# V-by-One.net
KiCad netlist of a schematic drawn in Altium Designer
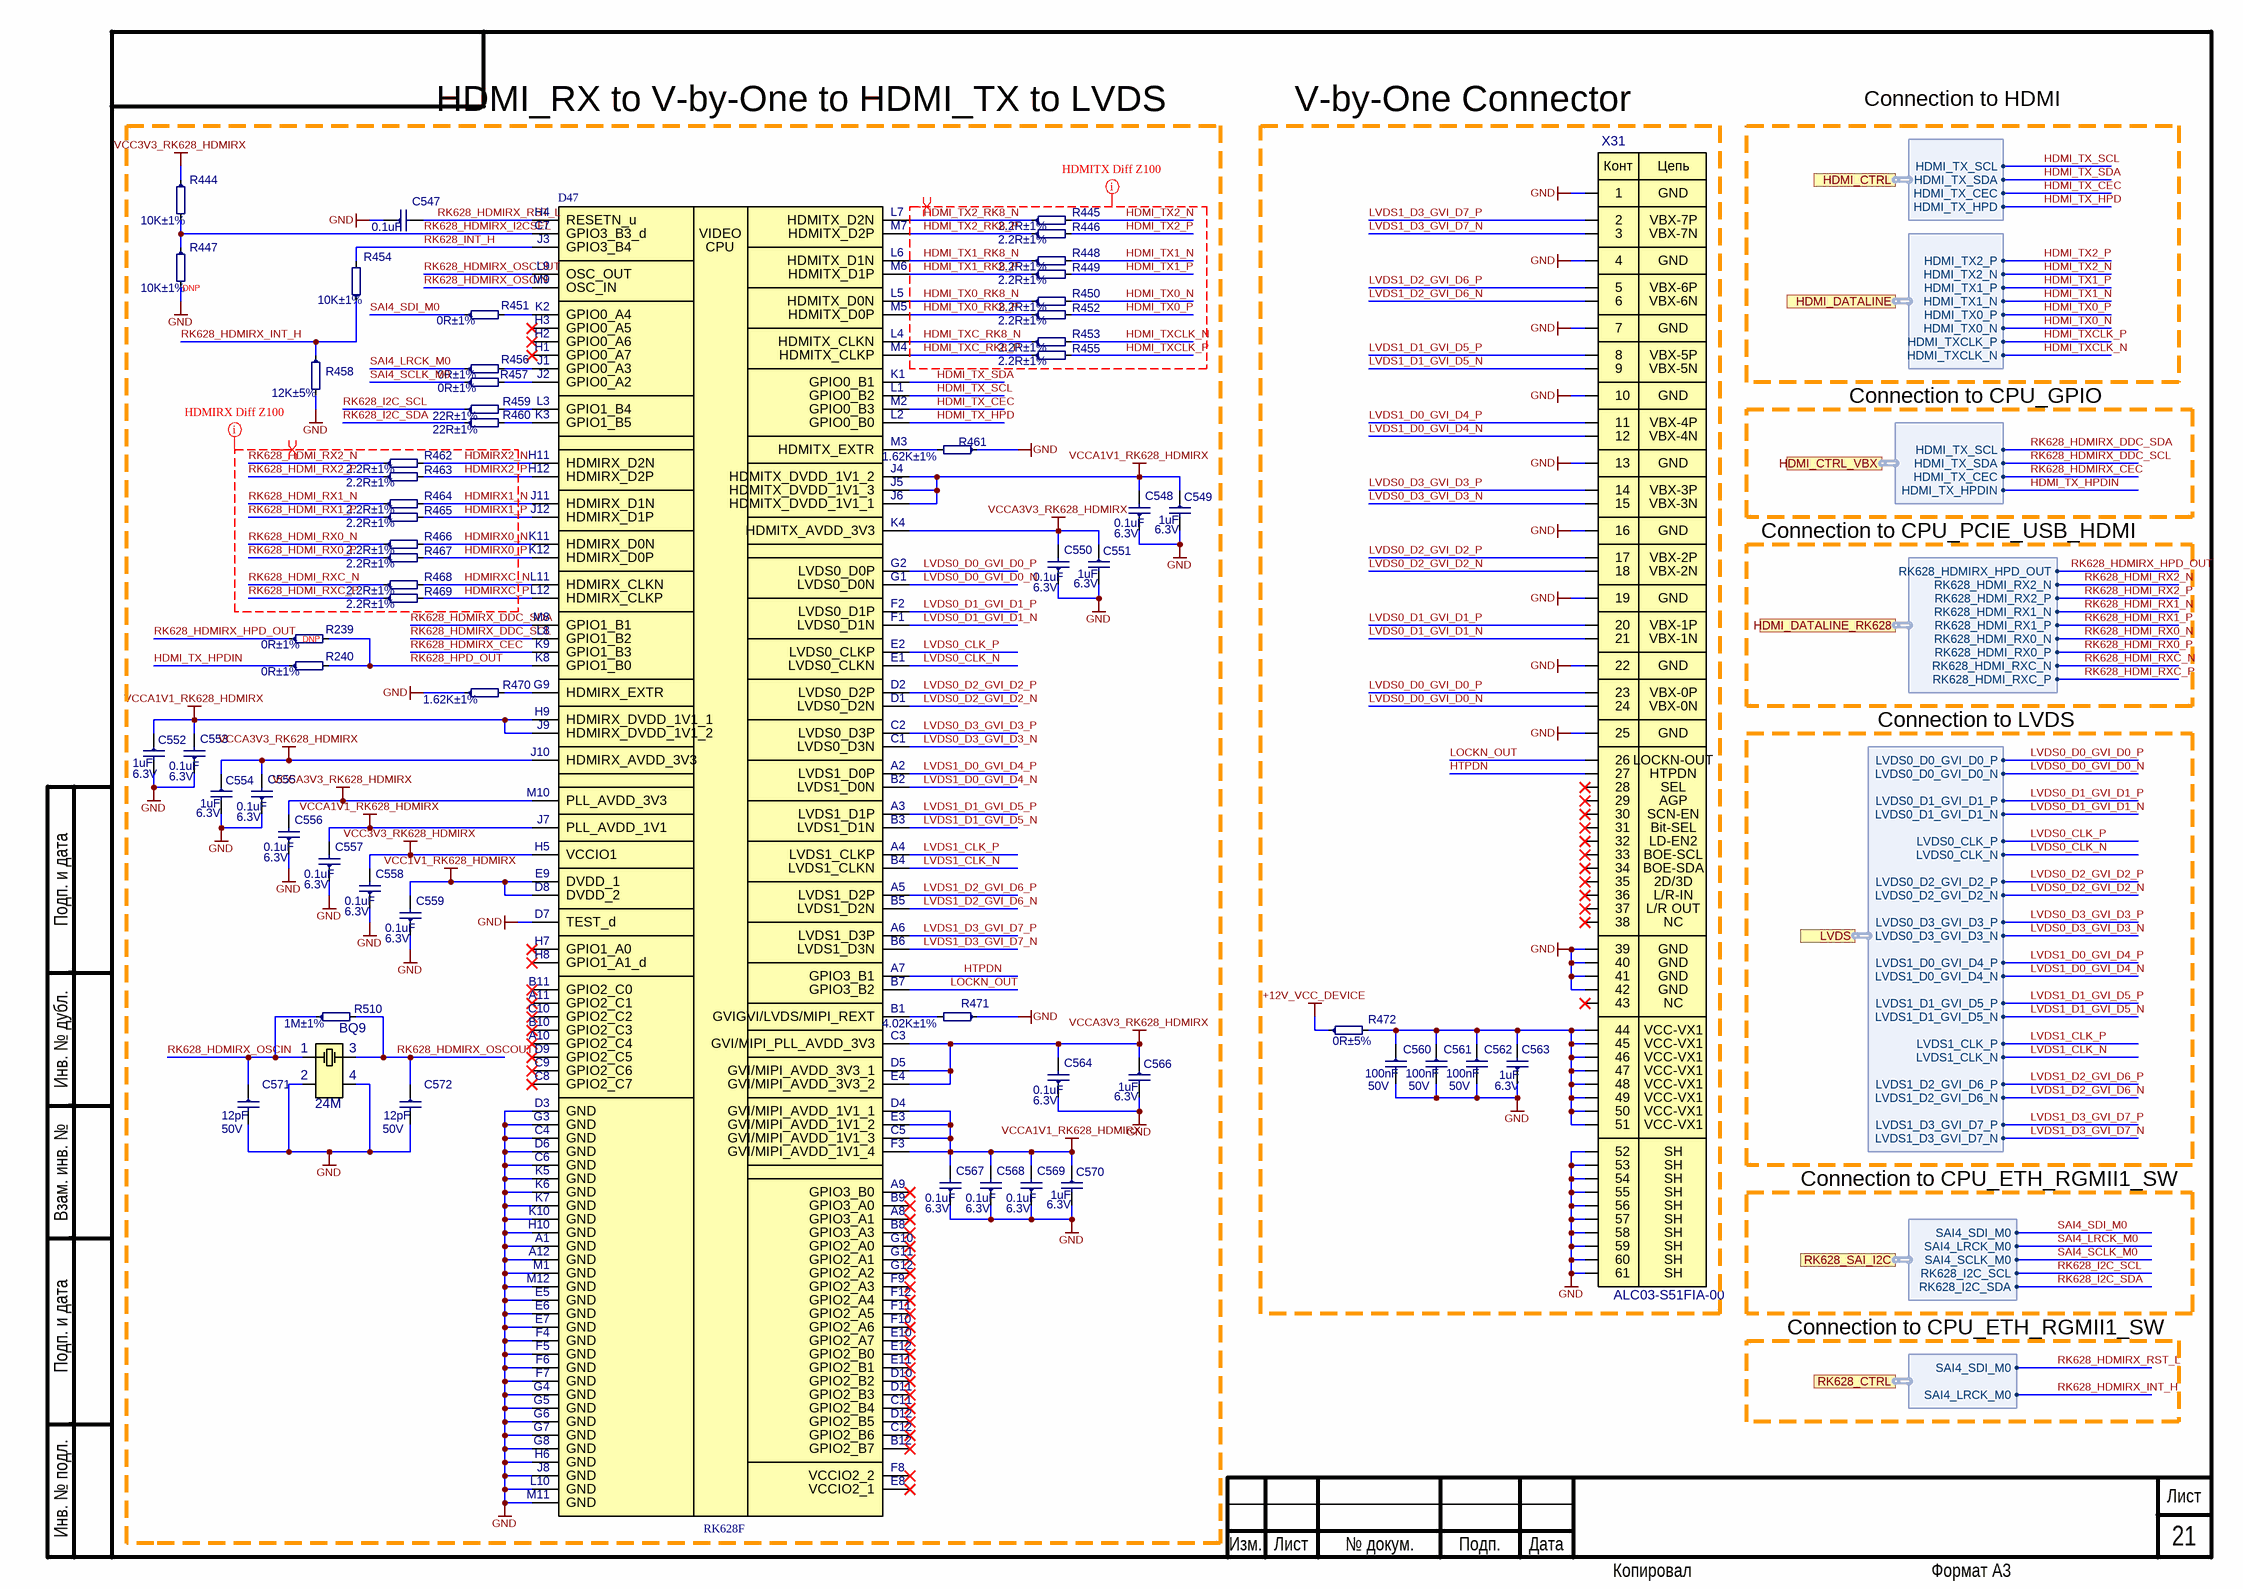
[diagram p0: V-by-One.SchDoc]

(export (version "E")
  (design (tool "Eeschema 10.0.6"))
  (components
    (comp (ref "BQ9")
      (value "24M")
      (footprint "NX3225GA")
      (fields
        (field (name "PART NUMBER") "3225-24-18-10-10/4B")
        (field (name "TOLERANCE") "10ppm")
        (field (name "MANUFACTURER") "Liming")
      )
      (libsource (lib "ATB") (part "BQ_4pin_2closed_2.4_2.4"))
    )
    (comp (ref "C547")
      (value "0.1uF")
      (footprint "C0201")
      (fields
        (field (name "VOLTAGE") "6.3V")
        (field (name "PART NUMBER") "0201-X5R-6.3V-0.1uF±10%")
        (field (name "TOLERANCE") "10%")
      )
      (libsource (lib "ATB") (part "C"))
    )
    (comp (ref "C548")
      (value "0.1uF")
      (footprint "C0201")
      (fields
        (field (name "VOLTAGE") "6.3V")
        (field (name "PART NUMBER") "0201-X5R-6.3V-0.1uF±10%")
        (field (name "TOLERANCE") "10%")
        (field (name "MANUFACTURER") "Yageo")
      )
      (libsource (lib "ATB") (part "C"))
    )
    (comp (ref "C549")
      (value "1uF")
      (footprint "C0201")
      (fields
        (field (name "VOLTAGE") "6.3V")
        (field (name "PART NUMBER") "0201-X5R-6.3V-1uF±20%")
        (field (name "TOLERANCE") "20%")
        (field (name "MANUFACTURER") "Murata Electronics")
      )
      (libsource (lib "ATB") (part "C"))
    )
    (comp (ref "C550")
      (value "0.1uF")
      (footprint "C0201")
      (fields
        (field (name "VOLTAGE") "6.3V")
        (field (name "PART NUMBER") "0201-X5R-6.3V-0.1uF±10%")
        (field (name "TOLERANCE") "10%")
        (field (name "MANUFACTURER") "Yageo")
      )
      (libsource (lib "ATB") (part "C"))
    )
    (comp (ref "C551")
      (value "1uF")
      (footprint "C0201")
      (fields
        (field (name "VOLTAGE") "6.3V")
        (field (name "PART NUMBER") "0201-X5R-6.3V-1uF±20%")
        (field (name "TOLERANCE") "20%")
        (field (name "MANUFACTURER") "Murata Electronics")
      )
      (libsource (lib "ATB") (part "C"))
    )
    (comp (ref "C552")
      (value "1uF")
      (footprint "C0201")
      (fields
        (field (name "VOLTAGE") "6.3V")
        (field (name "PART NUMBER") "0201-X5R-6.3V-1uF±20%")
        (field (name "TOLERANCE") "20%")
        (field (name "MANUFACTURER") "Murata Electronics")
      )
      (libsource (lib "ATB") (part "C"))
    )
    (comp (ref "C553")
      (value "0.1uF")
      (footprint "C0201")
      (fields
        (field (name "VOLTAGE") "6.3V")
        (field (name "PART NUMBER") "0201-X5R-6.3V-0.1uF±10%")
        (field (name "TOLERANCE") "10%")
        (field (name "MANUFACTURER") "Yageo")
      )
      (libsource (lib "ATB") (part "C"))
    )
    (comp (ref "C554")
      (value "1uF")
      (footprint "C0201")
      (fields
        (field (name "VOLTAGE") "6.3V")
        (field (name "PART NUMBER") "0201-X5R-6.3V-1uF±20%")
        (field (name "TOLERANCE") "20%")
        (field (name "MANUFACTURER") "Murata Electronics")
      )
      (libsource (lib "ATB") (part "C"))
    )
    (comp (ref "C555")
      (value "0.1uF")
      (footprint "C0201")
      (fields
        (field (name "VOLTAGE") "6.3V")
        (field (name "PART NUMBER") "0201-X5R-6.3V-0.1uF±10%")
        (field (name "TOLERANCE") "10%")
        (field (name "MANUFACTURER") "Yageo")
      )
      (libsource (lib "ATB") (part "C"))
    )
    (comp (ref "C556")
      (value "0.1uF")
      (footprint "C0201")
      (fields
        (field (name "VOLTAGE") "6.3V")
        (field (name "PART NUMBER") "0201-X5R-6.3V-0.1uF±10%")
        (field (name "TOLERANCE") "10%")
        (field (name "MANUFACTURER") "Yageo")
      )
      (libsource (lib "ATB") (part "C"))
    )
    (comp (ref "C557")
      (value "0.1uF")
      (footprint "C0201")
      (fields
        (field (name "VOLTAGE") "6.3V")
        (field (name "PART NUMBER") "0201-X5R-6.3V-0.1uF±10%")
        (field (name "TOLERANCE") "10%")
        (field (name "MANUFACTURER") "Yageo")
      )
      (libsource (lib "ATB") (part "C"))
    )
    (comp (ref "C558")
      (value "0.1uF")
      (footprint "C0201")
      (fields
        (field (name "VOLTAGE") "6.3V")
        (field (name "PART NUMBER") "0201-X5R-6.3V-0.1uF±10%")
        (field (name "TOLERANCE") "10%")
        (field (name "MANUFACTURER") "Yageo")
      )
      (libsource (lib "ATB") (part "C"))
    )
    (comp (ref "C559")
      (value "0.1uF")
      (footprint "C0201")
      (fields
        (field (name "VOLTAGE") "6.3V")
        (field (name "PART NUMBER") "0201-X5R-6.3V-0.1uF±10%")
        (field (name "TOLERANCE") "10%")
        (field (name "MANUFACTURER") "Yageo")
      )
      (libsource (lib "ATB") (part "C"))
    )
    (comp (ref "C560")
      (value "100nF")
      (footprint "C0402")
      (description "Ceramic Capacitor 0402 100nF ±10% 50V X7R")
      (fields
        (field (name "VOLTAGE") "50V")
        (field (name "PART NUMBER") "0402-X7R-50V-0.1uF±10%")
        (field (name "TOLERANCE") "10%")
      )
      (libsource (lib "ATB") (part "C"))
    )
    (comp (ref "C561")
      (value "100nF")
      (footprint "C0402")
      (description "Ceramic Capacitor 0402 100nF ±10% 50V X7R")
      (fields
        (field (name "VOLTAGE") "50V")
        (field (name "PART NUMBER") "0402-X7R-50V-0.1uF±10%")
        (field (name "TOLERANCE") "10%")
      )
      (libsource (lib "ATB") (part "C"))
    )
    (comp (ref "C562")
      (value "100nF")
      (footprint "C0402")
      (description "Ceramic Capacitor 0402 100nF ±10% 50V X7R")
      (fields
        (field (name "VOLTAGE") "50V")
        (field (name "PART NUMBER") "0402-X7R-50V-0.1uF±10%")
        (field (name "TOLERANCE") "10%")
      )
      (libsource (lib "ATB") (part "C"))
    )
    (comp (ref "C563")
      (value "1uF")
      (footprint "C0201")
      (fields
        (field (name "VOLTAGE") "6.3V")
        (field (name "PART NUMBER") "0201-X5R-6.3V-1uF±20%")
        (field (name "TOLERANCE") "20%")
        (field (name "MANUFACTURER") "Murata Electronics")
      )
      (libsource (lib "ATB") (part "C"))
    )
    (comp (ref "C564")
      (value "0.1uF")
      (footprint "C0201")
      (fields
        (field (name "VOLTAGE") "6.3V")
        (field (name "PART NUMBER") "0201-X5R-6.3V-0.1uF±10%")
        (field (name "TOLERANCE") "10%")
        (field (name "MANUFACTURER") "Yageo")
      )
      (libsource (lib "ATB") (part "C"))
    )
    (comp (ref "C566")
      (value "1uF")
      (footprint "C0201")
      (fields
        (field (name "VOLTAGE") "6.3V")
        (field (name "PART NUMBER") "0201-X5R-6.3V-1uF±20%")
        (field (name "TOLERANCE") "20%")
        (field (name "MANUFACTURER") "Murata Electronics")
      )
      (libsource (lib "ATB") (part "C"))
    )
    (comp (ref "C567")
      (value "0.1uF")
      (footprint "C0201")
      (fields
        (field (name "VOLTAGE") "6.3V")
        (field (name "PART NUMBER") "0201-X5R-6.3V-0.1uF±10%")
        (field (name "TOLERANCE") "10%")
        (field (name "MANUFACTURER") "Yageo")
      )
      (libsource (lib "ATB") (part "C"))
    )
    (comp (ref "C568")
      (value "0.1uF")
      (footprint "C0201")
      (fields
        (field (name "VOLTAGE") "6.3V")
        (field (name "PART NUMBER") "0201-X5R-6.3V-0.1uF±10%")
        (field (name "TOLERANCE") "10%")
        (field (name "MANUFACTURER") "Yageo")
      )
      (libsource (lib "ATB") (part "C"))
    )
    (comp (ref "C569")
      (value "0.1uF")
      (footprint "C0201")
      (fields
        (field (name "VOLTAGE") "6.3V")
        (field (name "PART NUMBER") "0201-X5R-6.3V-0.1uF±10%")
        (field (name "TOLERANCE") "10%")
        (field (name "MANUFACTURER") "Yageo")
      )
      (libsource (lib "ATB") (part "C"))
    )
    (comp (ref "C570")
      (value "1uF")
      (footprint "C0201")
      (fields
        (field (name "VOLTAGE") "6.3V")
        (field (name "PART NUMBER") "0201-X5R-6.3V-1uF±20%")
        (field (name "TOLERANCE") "20%")
        (field (name "MANUFACTURER") "Murata Electronics")
      )
      (libsource (lib "ATB") (part "C"))
    )
    (comp (ref "C571")
      (value "12pF")
      (footprint "C0402")
      (fields
        (field (name "VOLTAGE") "50V")
        (field (name "PART NUMBER") "0402-NP0-50V-12pF±5%")
        (field (name "TOLERANCE") "5%")
        (field (name "MANUFACTURER") "Murata Electronics")
      )
      (libsource (lib "ATB") (part "C"))
    )
    (comp (ref "C572")
      (value "12pF")
      (footprint "C0402")
      (fields
        (field (name "VOLTAGE") "50V")
        (field (name "PART NUMBER") "0402-NP0-50V-12pF±5%")
        (field (name "TOLERANCE") "5%")
        (field (name "MANUFACTURER") "Murata Electronics")
      )
      (libsource (lib "ATB") (part "C"))
    )
    (comp (ref "D47")
      (value "RK628F")
      (footprint "RK628F")
      (description "Bridge BGA-144L(8x8) Video Processing RoHS")
      (fields (field (name "MANUFACTURER") "Rockchip"))
      (libsource (lib "LIB_RK") (part "RK628F"))
    )
    (comp (ref "R239")
      (value "0R±1%")
      (footprint "R0402")
      (description "Chip Resistor 0402 0Ω ±1% 50V ±100ppm/℃ Thick Film")
      (fields (field (name "PART NUMBER") "0402-0.0625W-0R-100ppm±1%") (field (name "TOLERANCE") "1%"))
      (libsource (lib "ATB") (part "R"))
    )
    (comp (ref "R240")
      (value "0R±1%")
      (footprint "R0402")
      (description "Chip Resistor 0402 0Ω ±1% 50V ±100ppm/℃ Thick Film")
      (fields (field (name "PART NUMBER") "0402-0.0625W-0R-100ppm±1%") (field (name "TOLERANCE") "1%"))
      (libsource (lib "ATB") (part "R"))
    )
    (comp (ref "R444")
      (value "10K±1%")
      (footprint "R0402")
      (description "Chip Resistor 0402 10kΩ ±1% 50V ±100ppm/℃ Thick Film")
      (fields (field (name "PART NUMBER") "0402-0.0625W-10K-100ppm±1%") (field (name "TOLERANCE") "1%"))
      (libsource (lib "ATB") (part "R"))
    )
    (comp (ref "R445")
      (value "2.2R±1%")
      (footprint "R0402")
      (fields
        (field (name "PART NUMBER") "0402-0.0625W-2.2R-100ppm±1%")
        (field (name "TOLERANCE") "1%")
        (field (name "MANUFACTURER") "Yageo")
      )
      (libsource (lib "ATB") (part "R"))
    )
    (comp (ref "R446")
      (value "2.2R±1%")
      (footprint "R0402")
      (fields
        (field (name "PART NUMBER") "0402-0.0625W-2.2R-100ppm±1%")
        (field (name "TOLERANCE") "1%")
        (field (name "MANUFACTURER") "Yageo")
      )
      (libsource (lib "ATB") (part "R"))
    )
    (comp (ref "R447")
      (value "10K±1%")
      (footprint "R0402")
      (description "Chip Resistor 0402 10kΩ ±1% 50V ±100ppm/℃ Thick Film")
      (fields (field (name "PART NUMBER") "0402-0.0625W-10K-100ppm±1%") (field (name "TOLERANCE") "1%"))
      (libsource (lib "ATB") (part "R"))
    )
    (comp (ref "R448")
      (value "2.2R±1%")
      (footprint "R0402")
      (fields
        (field (name "PART NUMBER") "0402-0.0625W-2.2R-100ppm±1%")
        (field (name "TOLERANCE") "1%")
        (field (name "MANUFACTURER") "Yageo")
      )
      (libsource (lib "ATB") (part "R"))
    )
    (comp (ref "R449")
      (value "2.2R±1%")
      (footprint "R0402")
      (fields
        (field (name "PART NUMBER") "0402-0.0625W-2.2R-100ppm±1%")
        (field (name "TOLERANCE") "1%")
        (field (name "MANUFACTURER") "Yageo")
      )
      (libsource (lib "ATB") (part "R"))
    )
    (comp (ref "R450")
      (value "2.2R±1%")
      (footprint "R0402")
      (fields
        (field (name "PART NUMBER") "0402-0.0625W-2.2R-100ppm±1%")
        (field (name "TOLERANCE") "1%")
        (field (name "MANUFACTURER") "Yageo")
      )
      (libsource (lib "ATB") (part "R"))
    )
    (comp (ref "R451")
      (value "0R±1%")
      (footprint "R0402")
      (description "Chip Resistor 0402 0Ω ±1% 50V ±100ppm/℃ Thick Film")
      (fields (field (name "PART NUMBER") "0402-0.0625W-0R-100ppm±1%") (field (name "TOLERANCE") "1%"))
      (libsource (lib "ATB") (part "R"))
    )
    (comp (ref "R452")
      (value "2.2R±1%")
      (footprint "R0402")
      (fields
        (field (name "PART NUMBER") "0402-0.0625W-2.2R-100ppm±1%")
        (field (name "TOLERANCE") "1%")
        (field (name "MANUFACTURER") "Yageo")
      )
      (libsource (lib "ATB") (part "R"))
    )
    (comp (ref "R453")
      (value "2.2R±1%")
      (footprint "R0402")
      (fields
        (field (name "PART NUMBER") "0402-0.0625W-2.2R-100ppm±1%")
        (field (name "TOLERANCE") "1%")
        (field (name "MANUFACTURER") "Yageo")
      )
      (libsource (lib "ATB") (part "R"))
    )
    (comp (ref "R454")
      (value "10K±1%")
      (footprint "R0402")
      (description "Chip Resistor 0402 10kΩ ±1% 50V ±100ppm/℃ Thick Film")
      (fields (field (name "PART NUMBER") "0402-0.0625W-10K-100ppm±1%") (field (name "TOLERANCE") "1%"))
      (libsource (lib "ATB") (part "R"))
    )
    (comp (ref "R455")
      (value "2.2R±1%")
      (footprint "R0402")
      (fields
        (field (name "PART NUMBER") "0402-0.0625W-2.2R-100ppm±1%")
        (field (name "TOLERANCE") "1%")
        (field (name "MANUFACTURER") "Yageo")
      )
      (libsource (lib "ATB") (part "R"))
    )
    (comp (ref "R456")
      (value "0R±1%")
      (footprint "R0402")
      (description "Chip Resistor 0402 0Ω ±1% 50V ±100ppm/℃ Thick Film")
      (fields (field (name "PART NUMBER") "0402-0.0625W-0R-100ppm±1%") (field (name "TOLERANCE") "1%"))
      (libsource (lib "ATB") (part "R"))
    )
    (comp (ref "R457")
      (value "0R±1%")
      (footprint "R0402")
      (description "Chip Resistor 0402 0Ω ±1% 50V ±100ppm/℃ Thick Film")
      (fields (field (name "PART NUMBER") "0402-0.0625W-0R-100ppm±1%") (field (name "TOLERANCE") "1%"))
      (libsource (lib "ATB") (part "R"))
    )
    (comp (ref "R458")
      (value "12K±5%")
      (footprint "R0402")
      (fields
        (field (name "PART NUMBER") "0402-0.0625W-12K-100ppm±5%")
        (field (name "TOLERANCE") "5%")
        (field (name "MANUFACTURER") "Walsin Technology Corporation")
      )
      (libsource (lib "ATB") (part "R"))
    )
    (comp (ref "R459")
      (value "22R±1%")
      (footprint "R0402")
      (description "Chip Resistor 0402 22Ω ±1% 50V ±100ppm/℃ Thick Film")
      (fields (field (name "PART NUMBER") "0402-0.0625W-22R-100ppm±1%") (field (name "TOLERANCE") "1%"))
      (libsource (lib "ATB") (part "R"))
    )
    (comp (ref "R460")
      (value "22R±1%")
      (footprint "R0402")
      (description "Chip Resistor 0402 22Ω ±1% 50V ±100ppm/℃ Thick Film")
      (fields (field (name "PART NUMBER") "0402-0.0625W-22R-100ppm±1%") (field (name "TOLERANCE") "1%"))
      (libsource (lib "ATB") (part "R"))
    )
    (comp (ref "R461")
      (value "1.62K±1%")
      (footprint "R0402")
      (fields
        (field (name "PART NUMBER") "0402-0.0625W-1.62K-100ppm±1%")
        (field (name "TOLERANCE") "1%")
        (field (name "MANUFACTURER") "Yageo")
      )
      (libsource (lib "ATB") (part "R"))
    )
    (comp (ref "R462")
      (value "2.2R±1%")
      (footprint "R0402")
      (fields
        (field (name "PART NUMBER") "0402-0.0625W-2.2R-100ppm±1%")
        (field (name "TOLERANCE") "1%")
        (field (name "MANUFACTURER") "Yageo")
      )
      (libsource (lib "ATB") (part "R"))
    )
    (comp (ref "R463")
      (value "2.2R±1%")
      (footprint "R0402")
      (fields
        (field (name "PART NUMBER") "0402-0.0625W-2.2R-100ppm±1%")
        (field (name "TOLERANCE") "1%")
        (field (name "MANUFACTURER") "Yageo")
      )
      (libsource (lib "ATB") (part "R"))
    )
    (comp (ref "R464")
      (value "2.2R±1%")
      (footprint "R0402")
      (fields
        (field (name "PART NUMBER") "0402-0.0625W-2.2R-100ppm±1%")
        (field (name "TOLERANCE") "1%")
        (field (name "MANUFACTURER") "Yageo")
      )
      (libsource (lib "ATB") (part "R"))
    )
    (comp (ref "R465")
      (value "2.2R±1%")
      (footprint "R0402")
      (fields
        (field (name "PART NUMBER") "0402-0.0625W-2.2R-100ppm±1%")
        (field (name "TOLERANCE") "1%")
        (field (name "MANUFACTURER") "Yageo")
      )
      (libsource (lib "ATB") (part "R"))
    )
    (comp (ref "R466")
      (value "2.2R±1%")
      (footprint "R0402")
      (fields
        (field (name "PART NUMBER") "0402-0.0625W-2.2R-100ppm±1%")
        (field (name "TOLERANCE") "1%")
        (field (name "MANUFACTURER") "Yageo")
      )
      (libsource (lib "ATB") (part "R"))
    )
    (comp (ref "R467")
      (value "2.2R±1%")
      (footprint "R0402")
      (fields
        (field (name "PART NUMBER") "0402-0.0625W-2.2R-100ppm±1%")
        (field (name "TOLERANCE") "1%")
        (field (name "MANUFACTURER") "Yageo")
      )
      (libsource (lib "ATB") (part "R"))
    )
    (comp (ref "R468")
      (value "2.2R±1%")
      (footprint "R0402")
      (fields
        (field (name "PART NUMBER") "0402-0.0625W-2.2R-100ppm±1%")
        (field (name "TOLERANCE") "1%")
        (field (name "MANUFACTURER") "Yageo")
      )
      (libsource (lib "ATB") (part "R"))
    )
    (comp (ref "R469")
      (value "2.2R±1%")
      (footprint "R0402")
      (fields
        (field (name "PART NUMBER") "0402-0.0625W-2.2R-100ppm±1%")
        (field (name "TOLERANCE") "1%")
        (field (name "MANUFACTURER") "Yageo")
      )
      (libsource (lib "ATB") (part "R"))
    )
    (comp (ref "R470")
      (value "1.62K±1%")
      (footprint "R0402")
      (fields
        (field (name "PART NUMBER") "0402-0.0625W-1.62K-100ppm±1%")
        (field (name "TOLERANCE") "1%")
        (field (name "MANUFACTURER") "Yageo")
      )
      (libsource (lib "ATB") (part "R"))
    )
    (comp (ref "R471")
      (value "4.02K±1%")
      (footprint "R0402")
      (fields
        (field (name "PART NUMBER") "0402-0.0625W-4.02K-100ppm±1%")
        (field (name "TOLERANCE") "1%")
        (field (name "MANUFACTURER") "Yageo")
      )
      (libsource (lib "ATB") (part "R"))
    )
    (comp (ref "R472")
      (value "0R±5%")
      (footprint "R2010")
      (description "Chip Resistor 2010 0Ω ±5% 200V ±200ppm/℃ Thick Film")
      (fields (field (name "PART NUMBER") "2010-0.75W-0R-200ppm±5%") (field (name "TOLERANCE") "5%"))
      (libsource (lib "ATB") (part "R"))
    )
    (comp (ref "R510")
      (value "1M±1%")
      (footprint "R0402")
      (description "Chip Resistor 0402 1MΩ ±1% 50V ±100ppm/℃ Thick Film")
      (fields (field (name "PART NUMBER") "0402-0.0625W-1M-100ppm±1%") (field (name "TOLERANCE") "1%"))
      (libsource (lib "ATB") (part "R"))
    )
    (comp (ref "X31")
      (value "ALC03-S51FIA-00")
      (footprint "ALC03-S51FIA-00")
      (fields (field (name "MANUFACTURER") "JUSHUO"))
      (libsource (lib "LIB_RK") (part "ALC03-S51FIA-00"))
    )
  )
  (nets
    (net (code "8") (name "+12V_VCC_DEVICE") (class "Default")
      (node (ref "R472") (pin "1") (pinfunction "1_1") (pintype "passive"))
    )
    (net (code "9") (name "/HDMIRX0_N") (class "Default")
      (node (ref "D47") (pin "K11") (pinfunction "HDMIRX_D0N_K11") (pintype "passive"))
      (node (ref "R466") (pin "2") (pinfunction "2_2") (pintype "passive"))
    )
    (net (code "10") (name "/HDMIRX0_P") (class "Default")
      (node (ref "D47") (pin "K12") (pinfunction "HDMIRX_D0P_K12") (pintype "passive"))
      (node (ref "R467") (pin "2") (pinfunction "2_2") (pintype "passive"))
    )
    (net (code "11") (name "/HDMIRX1_N") (class "Default")
      (node (ref "D47") (pin "J11") (pinfunction "HDMIRX_D1N_J11") (pintype "passive"))
      (node (ref "R464") (pin "2") (pinfunction "2_2") (pintype "passive"))
    )
    (net (code "12") (name "/HDMIRX1_P") (class "Default")
      (node (ref "D47") (pin "J12") (pinfunction "HDMIRX_D1P_J12") (pintype "passive"))
      (node (ref "R465") (pin "2") (pinfunction "2_2") (pintype "passive"))
    )
    (net (code "13") (name "/HDMIRX2_N") (class "Default")
      (node (ref "D47") (pin "H11") (pinfunction "HDMIRX_D2N_H11") (pintype "passive"))
      (node (ref "R462") (pin "2") (pinfunction "2_2") (pintype "passive"))
    )
    (net (code "14") (name "/HDMIRX2_P") (class "Default")
      (node (ref "D47") (pin "H12") (pinfunction "HDMIRX_D2P_H12") (pintype "passive"))
      (node (ref "R463") (pin "2") (pinfunction "2_2") (pintype "passive"))
    )
    (net (code "15") (name "/HDMIRXC_N") (class "Default")
      (node (ref "D47") (pin "L11") (pinfunction "HDMIRX_CLKN_L11") (pintype "passive"))
      (node (ref "R468") (pin "2") (pinfunction "2_2") (pintype "passive"))
    )
    (net (code "16") (name "/HDMIRXC_P") (class "Default")
      (node (ref "D47") (pin "L12") (pinfunction "HDMIRX_CLKP_L12") (pintype "passive"))
      (node (ref "R469") (pin "2") (pinfunction "2_2") (pintype "passive"))
    )
    (net (code "17") (name "/HDMI_TX0_N") (class "Default")
      (node (ref "R450") (pin "2") (pinfunction "2_2") (pintype "passive"))
    )
    (net (code "18") (name "/HDMI_TX0_P") (class "Default")
      (node (ref "R452") (pin "2") (pinfunction "2_2") (pintype "passive"))
    )
    (net (code "19") (name "/HDMI_TX0_RK8_N") (class "Default")
      (node (ref "D47") (pin "L5") (pinfunction "HDMITX_D0N_L5") (pintype "passive"))
      (node (ref "R450") (pin "1") (pinfunction "1_1") (pintype "passive"))
    )
    (net (code "20") (name "/HDMI_TX0_RK8_P") (class "Default")
      (node (ref "D47") (pin "M5") (pinfunction "HDMITX_D0P_M5") (pintype "passive"))
      (node (ref "R452") (pin "1") (pinfunction "1_1") (pintype "passive"))
    )
    (net (code "21") (name "/HDMI_TX1_N") (class "Default")
      (node (ref "R448") (pin "2") (pinfunction "2_2") (pintype "passive"))
    )
    (net (code "22") (name "/HDMI_TX1_P") (class "Default")
      (node (ref "R449") (pin "2") (pinfunction "2_2") (pintype "passive"))
    )
    (net (code "23") (name "/HDMI_TX1_RK8_N") (class "Default")
      (node (ref "D47") (pin "L6") (pinfunction "HDMITX_D1N_L6") (pintype "passive"))
      (node (ref "R448") (pin "1") (pinfunction "1_1") (pintype "passive"))
    )
    (net (code "24") (name "/HDMI_TX1_RK8_P") (class "Default")
      (node (ref "D47") (pin "M6") (pinfunction "HDMITX_D1P_M6") (pintype "passive"))
      (node (ref "R449") (pin "1") (pinfunction "1_1") (pintype "passive"))
    )
    (net (code "25") (name "/HDMI_TX2_N") (class "Default")
      (node (ref "R445") (pin "2") (pinfunction "2_2") (pintype "passive"))
    )
    (net (code "26") (name "/HDMI_TX2_P") (class "Default")
      (node (ref "R446") (pin "2") (pinfunction "2_2") (pintype "passive"))
    )
    (net (code "27") (name "/HDMI_TX2_RK8_N") (class "Default")
      (node (ref "D47") (pin "L7") (pinfunction "HDMITX_D2N_L7") (pintype "passive"))
      (node (ref "R445") (pin "1") (pinfunction "1_1") (pintype "passive"))
    )
    (net (code "28") (name "/HDMI_TX2_RK8_P") (class "Default")
      (node (ref "D47") (pin "M7") (pinfunction "HDMITX_D2P_M7") (pintype "passive"))
      (node (ref "R446") (pin "1") (pinfunction "1_1") (pintype "passive"))
    )
    (net (code "29") (name "/HDMI_TXCLK_N") (class "Default")
      (node (ref "R453") (pin "2") (pinfunction "2_2") (pintype "passive"))
    )
    (net (code "30") (name "/HDMI_TXCLK_P") (class "Default")
      (node (ref "R455") (pin "2") (pinfunction "2_2") (pintype "passive"))
    )
    (net (code "31") (name "/HDMI_TXC_RK8_N") (class "Default")
      (node (ref "D47") (pin "L4") (pinfunction "HDMITX_CLKN_L4") (pintype "passive"))
      (node (ref "R453") (pin "1") (pinfunction "1_1") (pintype "passive"))
    )
    (net (code "32") (name "/HDMI_TXC_RK8_P") (class "Default")
      (node (ref "D47") (pin "M4") (pinfunction "HDMITX_CLKP_M4") (pintype "passive"))
      (node (ref "R455") (pin "1") (pinfunction "1_1") (pintype "passive"))
    )
    (net (code "33") (name "/HDMI_TX_CEC") (class "Default")
      (node (ref "D47") (pin "M2") (pinfunction "GPIO0_B3_M2") (pintype "passive"))
    )
    (net (code "34") (name "/HDMI_TX_HPD") (class "Default")
      (node (ref "D47") (pin "L2") (pinfunction "GPIO0_B0_L2") (pintype "passive"))
    )
    (net (code "35") (name "/HDMI_TX_HPDIN") (class "Default")
      (node (ref "R240") (pin "1") (pinfunction "1_1") (pintype "passive"))
    )
    (net (code "36") (name "/HDMI_TX_SCL") (class "Default")
      (node (ref "D47") (pin "L1") (pinfunction "GPIO0_B2_L1") (pintype "passive"))
    )
    (net (code "37") (name "/HDMI_TX_SDA") (class "Default")
      (node (ref "D47") (pin "K1") (pinfunction "GPIO0_B1_K1") (pintype "passive"))
    )
    (net (code "38") (name "/HTPDN") (class "Default")
      (node (ref "D47") (pin "A7") (pinfunction "GPIO3_B1_A7") (pintype "passive"))
      (node (ref "X31") (pin "27") (pinfunction "27_27") (pintype "passive"))
    )
    (net (code "39") (name "/LOCKN_OUT") (class "Default")
      (node (ref "D47") (pin "B7") (pinfunction "GPIO3_B2_B7") (pintype "passive"))
      (node (ref "X31") (pin "26") (pinfunction "26_26") (pintype "passive"))
    )
    (net (code "40") (name "/LVDS0_CLK_N") (class "Default")
      (node (ref "D47") (pin "E1") (pinfunction "LVDS0_CLKN_E1") (pintype "passive"))
    )
    (net (code "41") (name "/LVDS0_CLK_P") (class "Default")
      (node (ref "D47") (pin "E2") (pinfunction "LVDS0_CLKP_E2") (pintype "passive"))
    )
    (net (code "42") (name "/LVDS0_D0_GVI_D0_N") (class "Default")
      (node (ref "D47") (pin "G1") (pinfunction "LVDS0_D0N_G1") (pintype "passive"))
      (node (ref "X31") (pin "24") (pinfunction "24_24") (pintype "passive"))
    )
    (net (code "43") (name "/LVDS0_D0_GVI_D0_P") (class "Default")
      (node (ref "D47") (pin "G2") (pinfunction "LVDS0_D0P_G2") (pintype "passive"))
      (node (ref "X31") (pin "23") (pinfunction "23_23") (pintype "passive"))
    )
    (net (code "44") (name "/LVDS0_D1_GVI_D1_N") (class "Default")
      (node (ref "D47") (pin "F1") (pinfunction "LVDS0_D1N_F1") (pintype "passive"))
      (node (ref "X31") (pin "21") (pinfunction "21_21") (pintype "passive"))
    )
    (net (code "45") (name "/LVDS0_D1_GVI_D1_P") (class "Default")
      (node (ref "D47") (pin "F2") (pinfunction "LVDS0_D1P_F2") (pintype "passive"))
      (node (ref "X31") (pin "20") (pinfunction "20_20") (pintype "passive"))
    )
    (net (code "46") (name "/LVDS0_D2_GVI_D2_N") (class "Default")
      (node (ref "D47") (pin "D1") (pinfunction "LVDS0_D2N_D1") (pintype "passive"))
      (node (ref "X31") (pin "18") (pinfunction "18_18") (pintype "passive"))
    )
    (net (code "47") (name "/LVDS0_D2_GVI_D2_P") (class "Default")
      (node (ref "D47") (pin "D2") (pinfunction "LVDS0_D2P_D2") (pintype "passive"))
      (node (ref "X31") (pin "17") (pinfunction "17_17") (pintype "passive"))
    )
    (net (code "48") (name "/LVDS0_D3_GVI_D3_N") (class "Default")
      (node (ref "D47") (pin "C1") (pinfunction "LVDS0_D3N_C1") (pintype "passive"))
      (node (ref "X31") (pin "15") (pinfunction "15_15") (pintype "passive"))
    )
    (net (code "49") (name "/LVDS0_D3_GVI_D3_P") (class "Default")
      (node (ref "D47") (pin "C2") (pinfunction "LVDS0_D3P_C2") (pintype "passive"))
      (node (ref "X31") (pin "14") (pinfunction "14_14") (pintype "passive"))
    )
    (net (code "50") (name "/LVDS1_CLK_N") (class "Default")
      (node (ref "D47") (pin "B4") (pinfunction "LVDS1_CLKN_B4") (pintype "passive"))
    )
    (net (code "51") (name "/LVDS1_CLK_P") (class "Default")
      (node (ref "D47") (pin "A4") (pinfunction "LVDS1_CLKP_A4") (pintype "passive"))
    )
    (net (code "52") (name "/LVDS1_D0_GVI_D4_N") (class "Default")
      (node (ref "D47") (pin "B2") (pinfunction "LVDS1_D0N_B2") (pintype "passive"))
      (node (ref "X31") (pin "12") (pinfunction "12_12") (pintype "passive"))
    )
    (net (code "53") (name "/LVDS1_D0_GVI_D4_P") (class "Default")
      (node (ref "D47") (pin "A2") (pinfunction "LVDS1_D0P_A2") (pintype "passive"))
      (node (ref "X31") (pin "11") (pinfunction "11_11") (pintype "passive"))
    )
    (net (code "54") (name "/LVDS1_D1_GVI_D5_N") (class "Default")
      (node (ref "D47") (pin "B3") (pinfunction "LVDS1_D1N_B3") (pintype "passive"))
      (node (ref "X31") (pin "9") (pinfunction "9_9") (pintype "passive"))
    )
    (net (code "55") (name "/LVDS1_D1_GVI_D5_P") (class "Default")
      (node (ref "D47") (pin "A3") (pinfunction "LVDS1_D1P_A3") (pintype "passive"))
      (node (ref "X31") (pin "8") (pinfunction "8_8") (pintype "passive"))
    )
    (net (code "56") (name "/LVDS1_D2_GVI_D6_N") (class "Default")
      (node (ref "D47") (pin "B5") (pinfunction "LVDS1_D2N_B5") (pintype "passive"))
      (node (ref "X31") (pin "6") (pinfunction "6_6") (pintype "passive"))
    )
    (net (code "57") (name "/LVDS1_D2_GVI_D6_P") (class "Default")
      (node (ref "D47") (pin "A5") (pinfunction "LVDS1_D2P_A5") (pintype "passive"))
      (node (ref "X31") (pin "5") (pinfunction "5_5") (pintype "passive"))
    )
    (net (code "58") (name "/LVDS1_D3_GVI_D7_N") (class "Default")
      (node (ref "D47") (pin "B6") (pinfunction "LVDS1_D3N_B6") (pintype "passive"))
      (node (ref "X31") (pin "3") (pinfunction "3_3") (pintype "passive"))
    )
    (net (code "59") (name "/LVDS1_D3_GVI_D7_P") (class "Default")
      (node (ref "D47") (pin "A6") (pinfunction "LVDS1_D3P_A6") (pintype "passive"))
      (node (ref "X31") (pin "2") (pinfunction "2_2") (pintype "passive"))
    )
    (net (code "60") (name "/RK628_HDMIRX_CEC") (class "Default")
      (node (ref "D47") (pin "K9") (pinfunction "GPIO1_B3_K9") (pintype "passive"))
    )
    (net (code "61") (name "/RK628_HDMIRX_DDC_SCL") (class "Default")
      (node (ref "D47") (pin "L8") (pinfunction "GPIO1_B2_L8") (pintype "passive"))
    )
    (net (code "62") (name "/RK628_HDMIRX_DDC_SDA") (class "Default")
      (node (ref "D47") (pin "M8") (pinfunction "GPIO1_B1_M8") (pintype "passive"))
    )
    (net (code "63") (name "/RK628_HDMIRX_HPD_OUT") (class "Default")
      (node (ref "R239") (pin "1") (pinfunction "1_1") (pintype "passive"))
    )
    (net (code "64") (name "/RK628_HDMIRX_I2CSEL") (class "Default")
      (node (ref "D47") (pin "C7") (pinfunction "GPIO3_B3_d_C7") (pintype "passive"))
      (node (ref "R444") (pin "2") (pinfunction "2_2") (pintype "passive"))
      (node (ref "R447") (pin "1") (pinfunction "1_1") (pintype "passive"))
    )
    (net (code "65") (name "/RK628_HDMIRX_INT_H") (class "Default")
      (node (ref "R454") (pin "1") (pinfunction "1_1") (pintype "passive"))
      (node (ref "R458") (pin "1") (pinfunction "1_1") (pintype "passive"))
    )
    (net (code "66") (name "/RK628_HDMIRX_OSCIN") (class "Default")
      (node (ref "BQ9") (pin "1") (pinfunction "1_1") (pintype "passive"))
      (node (ref "C571") (pin "1") (pinfunction "1_1") (pintype "passive"))
      (node (ref "D47") (pin "M9") (pinfunction "OSC_IN_M9") (pintype "passive"))
      (node (ref "R510") (pin "1") (pinfunction "1_1") (pintype "passive"))
    )
    (net (code "67") (name "/RK628_HDMIRX_OSCOUT") (class "Default")
      (node (ref "BQ9") (pin "3") (pinfunction "3_3") (pintype "passive"))
      (node (ref "C572") (pin "1") (pinfunction "1_1") (pintype "passive"))
      (node (ref "D47") (pin "L9") (pinfunction "OSC_OUT_L9") (pintype "passive"))
      (node (ref "R510") (pin "2") (pinfunction "2_2") (pintype "passive"))
    )
    (net (code "68") (name "/RK628_HDMIRX_RST_L") (class "Default")
      (node (ref "C547") (pin "2") (pinfunction "2_2") (pintype "passive"))
      (node (ref "D47") (pin "H4") (pinfunction "RESETN_u_H4") (pintype "passive"))
    )
    (net (code "69") (name "/RK628_HDMI_RX0_N") (class "Default")
      (node (ref "R466") (pin "1") (pinfunction "1_1") (pintype "passive"))
    )
    (net (code "70") (name "/RK628_HDMI_RX0_P") (class "Default")
      (node (ref "R467") (pin "1") (pinfunction "1_1") (pintype "passive"))
    )
    (net (code "71") (name "/RK628_HDMI_RX1_N") (class "Default")
      (node (ref "R464") (pin "1") (pinfunction "1_1") (pintype "passive"))
    )
    (net (code "72") (name "/RK628_HDMI_RX1_P") (class "Default")
      (node (ref "R465") (pin "1") (pinfunction "1_1") (pintype "passive"))
    )
    (net (code "73") (name "/RK628_HDMI_RX2_N") (class "Default")
      (node (ref "R462") (pin "1") (pinfunction "1_1") (pintype "passive"))
    )
    (net (code "74") (name "/RK628_HDMI_RX2_P") (class "Default")
      (node (ref "R463") (pin "1") (pinfunction "1_1") (pintype "passive"))
    )
    (net (code "75") (name "/RK628_HDMI_RXC_N") (class "Default")
      (node (ref "R468") (pin "1") (pinfunction "1_1") (pintype "passive"))
    )
    (net (code "76") (name "/RK628_HDMI_RXC_P") (class "Default")
      (node (ref "R469") (pin "1") (pinfunction "1_1") (pintype "passive"))
    )
    (net (code "77") (name "/RK628_HPD_OUT") (class "Default")
      (node (ref "D47") (pin "K8") (pinfunction "GPIO1_B0_K8") (pintype "passive"))
      (node (ref "R239") (pin "2") (pinfunction "2_2") (pintype "passive"))
      (node (ref "R240") (pin "2") (pinfunction "2_2") (pintype "passive"))
    )
    (net (code "78") (name "/RK628_I2C_SCL") (class "Default")
      (node (ref "R459") (pin "1") (pinfunction "1_1") (pintype "passive"))
    )
    (net (code "79") (name "/RK628_I2C_SDA") (class "Default")
      (node (ref "R460") (pin "1") (pinfunction "1_1") (pintype "passive"))
    )
    (net (code "80") (name "/RK628_INT_H") (class "Default")
      (node (ref "D47") (pin "J3") (pinfunction "GPIO3_B4_J3") (pintype "passive"))
      (node (ref "R454") (pin "2") (pinfunction "2_2") (pintype "passive"))
    )
    (net (code "81") (name "/SAI4_LRCK_M0") (class "Default")
      (node (ref "R456") (pin "1") (pinfunction "1_1") (pintype "passive"))
    )
    (net (code "82") (name "/SAI4_SCLK_M0") (class "Default")
      (node (ref "R457") (pin "1") (pinfunction "1_1") (pintype "passive"))
    )
    (net (code "83") (name "/SAI4_SDI_M0") (class "Default")
      (node (ref "R451") (pin "1") (pinfunction "1_1") (pintype "passive"))
    )
    (net (code "91") (name "GND") (class "Default")
      (node (ref "BQ9") (pin "2") (pinfunction "2_2") (pintype "passive"))
      (node (ref "BQ9") (pin "4") (pinfunction "4_4") (pintype "passive"))
      (node (ref "C547") (pin "1") (pinfunction "1_1") (pintype "passive"))
      (node (ref "C548") (pin "1") (pinfunction "1_1") (pintype "passive"))
      (node (ref "C549") (pin "2") (pinfunction "2_2") (pintype "passive"))
      (node (ref "C550") (pin "1") (pinfunction "1_1") (pintype "passive"))
      (node (ref "C551") (pin "2") (pinfunction "2_2") (pintype "passive"))
      (node (ref "C552") (pin "2") (pinfunction "2_2") (pintype "passive"))
      (node (ref "C553") (pin "1") (pinfunction "1_1") (pintype "passive"))
      (node (ref "C554") (pin "2") (pinfunction "2_2") (pintype "passive"))
      (node (ref "C555") (pin "1") (pinfunction "1_1") (pintype "passive"))
      (node (ref "C556") (pin "1") (pinfunction "1_1") (pintype "passive"))
      (node (ref "C557") (pin "1") (pinfunction "1_1") (pintype "passive"))
      (node (ref "C558") (pin "1") (pinfunction "1_1") (pintype "passive"))
      (node (ref "C559") (pin "1") (pinfunction "1_1") (pintype "passive"))
      (node (ref "C560") (pin "2") (pinfunction "2_2") (pintype "passive"))
      (node (ref "C561") (pin "2") (pinfunction "2_2") (pintype "passive"))
      (node (ref "C562") (pin "2") (pinfunction "2_2") (pintype "passive"))
      (node (ref "C563") (pin "1") (pinfunction "1_1") (pintype "passive"))
      (node (ref "C564") (pin "1") (pinfunction "1_1") (pintype "passive"))
      (node (ref "C566") (pin "2") (pinfunction "2_2") (pintype "passive"))
      (node (ref "C567") (pin "1") (pinfunction "1_1") (pintype "passive"))
      (node (ref "C568") (pin "1") (pinfunction "1_1") (pintype "passive"))
      (node (ref "C569") (pin "1") (pinfunction "1_1") (pintype "passive"))
      (node (ref "C570") (pin "2") (pinfunction "2_2") (pintype "passive"))
      (node (ref "C571") (pin "2") (pinfunction "2_2") (pintype "passive"))
      (node (ref "C572") (pin "2") (pinfunction "2_2") (pintype "passive"))
      (node (ref "D47") (pin "A1") (pinfunction "GND_A1") (pintype "passive"))
      (node (ref "D47") (pin "A12") (pinfunction "GND_A12") (pintype "passive"))
      (node (ref "D47") (pin "C4") (pinfunction "GND_C4") (pintype "passive"))
      (node (ref "D47") (pin "C6") (pinfunction "GND_C6") (pintype "passive"))
      (node (ref "D47") (pin "D3") (pinfunction "GND_D3") (pintype "passive"))
      (node (ref "D47") (pin "D6") (pinfunction "GND_D6") (pintype "passive"))
      (node (ref "D47") (pin "D7") (pinfunction "TEST_d_D7") (pintype "passive"))
      (node (ref "D47") (pin "E5") (pinfunction "GND_E5") (pintype "passive"))
      (node (ref "D47") (pin "E6") (pinfunction "GND_E6") (pintype "passive"))
      (node (ref "D47") (pin "E7") (pinfunction "GND_E7") (pintype "passive"))
      (node (ref "D47") (pin "F4") (pinfunction "GND_F4") (pintype "passive"))
      (node (ref "D47") (pin "F5") (pinfunction "GND_F5") (pintype "passive"))
      (node (ref "D47") (pin "F6") (pinfunction "GND_F6") (pintype "passive"))
      (node (ref "D47") (pin "F7") (pinfunction "GND_F7") (pintype "passive"))
      (node (ref "D47") (pin "G3") (pinfunction "GND_G3") (pintype "passive"))
      (node (ref "D47") (pin "G4") (pinfunction "GND_G4") (pintype "passive"))
      (node (ref "D47") (pin "G5") (pinfunction "GND_G5") (pintype "passive"))
      (node (ref "D47") (pin "G6") (pinfunction "GND_G6") (pintype "passive"))
      (node (ref "D47") (pin "G7") (pinfunction "GND_G7") (pintype "passive"))
      (node (ref "D47") (pin "G8") (pinfunction "GND_G8") (pintype "passive"))
      (node (ref "D47") (pin "H10") (pinfunction "GND_H10") (pintype "passive"))
      (node (ref "D47") (pin "H6") (pinfunction "GND_H6") (pintype "passive"))
      (node (ref "D47") (pin "J8") (pinfunction "GND_J8") (pintype "passive"))
      (node (ref "D47") (pin "K10") (pinfunction "GND_K10") (pintype "passive"))
      (node (ref "D47") (pin "K5") (pinfunction "GND_K5") (pintype "passive"))
      (node (ref "D47") (pin "K6") (pinfunction "GND_K6") (pintype "passive"))
      (node (ref "D47") (pin "K7") (pinfunction "GND_K7") (pintype "passive"))
      (node (ref "D47") (pin "L10") (pinfunction "GND_L10") (pintype "passive"))
      (node (ref "D47") (pin "M1") (pinfunction "GND_M1") (pintype "passive"))
      (node (ref "D47") (pin "M11") (pinfunction "GND_M11") (pintype "passive"))
      (node (ref "D47") (pin "M12") (pinfunction "GND_M12") (pintype "passive"))
      (node (ref "R447") (pin "2") (pinfunction "2_2") (pintype "passive"))
      (node (ref "R458") (pin "2") (pinfunction "2_2") (pintype "passive"))
      (node (ref "R461") (pin "1") (pinfunction "1_1") (pintype "passive"))
      (node (ref "R470") (pin "1") (pinfunction "1_1") (pintype "passive"))
      (node (ref "R471") (pin "1") (pinfunction "1_1") (pintype "passive"))
      (node (ref "X31") (pin "1") (pinfunction "1_1") (pintype "passive"))
      (node (ref "X31") (pin "10") (pinfunction "10_10") (pintype "passive"))
      (node (ref "X31") (pin "13") (pinfunction "13_13") (pintype "passive"))
      (node (ref "X31") (pin "16") (pinfunction "16_16") (pintype "passive"))
      (node (ref "X31") (pin "19") (pinfunction "19_19") (pintype "passive"))
      (node (ref "X31") (pin "22") (pinfunction "22_22") (pintype "passive"))
      (node (ref "X31") (pin "25") (pinfunction "25_25") (pintype "passive"))
      (node (ref "X31") (pin "39") (pinfunction "39_39") (pintype "passive"))
      (node (ref "X31") (pin "4") (pinfunction "4_4") (pintype "passive"))
      (node (ref "X31") (pin "40") (pinfunction "40_40") (pintype "passive"))
      (node (ref "X31") (pin "41") (pinfunction "41_41") (pintype "passive"))
      (node (ref "X31") (pin "42") (pinfunction "42_42") (pintype "passive"))
      (node (ref "X31") (pin "52") (pinfunction "52_52") (pintype "passive"))
      (node (ref "X31") (pin "53") (pinfunction "53_53") (pintype "passive"))
      (node (ref "X31") (pin "54") (pinfunction "54_54") (pintype "passive"))
      (node (ref "X31") (pin "55") (pinfunction "55_55") (pintype "passive"))
      (node (ref "X31") (pin "56") (pinfunction "56_56") (pintype "passive"))
      (node (ref "X31") (pin "57") (pinfunction "57_57") (pintype "passive"))
      (node (ref "X31") (pin "58") (pinfunction "58_58") (pintype "passive"))
      (node (ref "X31") (pin "59") (pinfunction "59_59") (pintype "passive"))
      (node (ref "X31") (pin "60") (pinfunction "60_60") (pintype "passive"))
      (node (ref "X31") (pin "61") (pinfunction "61_61") (pintype "passive"))
      (node (ref "X31") (pin "7") (pinfunction "7_7") (pintype "passive"))
    )
    (net (code "92") (name "Net-(C560-Pad1)") (class "Default")
      (node (ref "C560") (pin "1") (pinfunction "1_1") (pintype "passive"))
      (node (ref "C561") (pin "1") (pinfunction "1_1") (pintype "passive"))
      (node (ref "C562") (pin "1") (pinfunction "1_1") (pintype "passive"))
      (node (ref "C563") (pin "2") (pinfunction "2_2") (pintype "passive"))
      (node (ref "R472") (pin "2") (pinfunction "2_2") (pintype "passive"))
      (node (ref "X31") (pin "44") (pinfunction "44_44") (pintype "passive"))
      (node (ref "X31") (pin "45") (pinfunction "45_45") (pintype "passive"))
      (node (ref "X31") (pin "46") (pinfunction "46_46") (pintype "passive"))
      (node (ref "X31") (pin "47") (pinfunction "47_47") (pintype "passive"))
      (node (ref "X31") (pin "48") (pinfunction "48_48") (pintype "passive"))
      (node (ref "X31") (pin "49") (pinfunction "49_49") (pintype "passive"))
      (node (ref "X31") (pin "50") (pinfunction "50_50") (pintype "passive"))
      (node (ref "X31") (pin "51") (pinfunction "51_51") (pintype "passive"))
    )
    (net (code "93") (name "Net-(D47-GPIO0_A2)") (class "Default")
      (node (ref "D47") (pin "J2") (pinfunction "GPIO0_A2_J2") (pintype "passive"))
      (node (ref "R457") (pin "2") (pinfunction "2_2") (pintype "passive"))
    )
    (net (code "94") (name "Net-(D47-GPIO0_A3)") (class "Default")
      (node (ref "D47") (pin "J1") (pinfunction "GPIO0_A3_J1") (pintype "passive"))
      (node (ref "R456") (pin "2") (pinfunction "2_2") (pintype "passive"))
    )
    (net (code "95") (name "Net-(D47-GPIO0_A4)") (class "Default")
      (node (ref "D47") (pin "K2") (pinfunction "GPIO0_A4_K2") (pintype "passive"))
      (node (ref "R451") (pin "2") (pinfunction "2_2") (pintype "passive"))
    )
    (net (code "96") (name "Net-(D47-GPIO1_B4)") (class "Default")
      (node (ref "D47") (pin "L3") (pinfunction "GPIO1_B4_L3") (pintype "passive"))
      (node (ref "R459") (pin "2") (pinfunction "2_2") (pintype "passive"))
    )
    (net (code "97") (name "Net-(D47-GPIO1_B5)") (class "Default")
      (node (ref "D47") (pin "K3") (pinfunction "GPIO1_B5_K3") (pintype "passive"))
      (node (ref "R460") (pin "2") (pinfunction "2_2") (pintype "passive"))
    )
    (net (code "98") (name "Net-(D47-GVIGVI{slash}LVDS{slash}MIPI_REXT)") (class "Default")
      (node (ref "D47") (pin "B1") (pinfunction "GVIGVI/LVDS/MIPI_REXT_B1") (pintype "passive"))
      (node (ref "R471") (pin "2") (pinfunction "2_2") (pintype "passive"))
    )
    (net (code "99") (name "Net-(D47-HDMIRX_EXTR)") (class "Default")
      (node (ref "D47") (pin "G9") (pinfunction "HDMIRX_EXTR_G9") (pintype "passive"))
      (node (ref "R470") (pin "2") (pinfunction "2_2") (pintype "passive"))
    )
    (net (code "100") (name "Net-(D47-HDMITX_EXTR)") (class "Default")
      (node (ref "D47") (pin "M3") (pinfunction "HDMITX_EXTR_M3") (pintype "passive"))
      (node (ref "R461") (pin "2") (pinfunction "2_2") (pintype "passive"))
    )
    (net (code "101") (name "VCC1V1_RK628_HDMIRX") (class "Default")
      (node (ref "C559") (pin "2") (pinfunction "2_2") (pintype "passive"))
      (node (ref "D47") (pin "D8") (pinfunction "DVDD_2_D8") (pintype "passive"))
      (node (ref "D47") (pin "E9") (pinfunction "DVDD_1_E9") (pintype "passive"))
    )
    (net (code "102") (name "VCC3V3_RK628_HDMIRX") (class "Default")
      (node (ref "C558") (pin "2") (pinfunction "2_2") (pintype "passive"))
      (node (ref "D47") (pin "H5") (pinfunction "VCCIO1_H5") (pintype "passive"))
      (node (ref "R444") (pin "1") (pinfunction "1_1") (pintype "passive"))
    )
    (net (code "103") (name "VCCA1V1_RK628_HDMIRX") (class "Default")
      (node (ref "C548") (pin "2") (pinfunction "2_2") (pintype "passive"))
      (node (ref "C549") (pin "1") (pinfunction "1_1") (pintype "passive"))
      (node (ref "C552") (pin "1") (pinfunction "1_1") (pintype "passive"))
      (node (ref "C553") (pin "2") (pinfunction "2_2") (pintype "passive"))
      (node (ref "C557") (pin "2") (pinfunction "2_2") (pintype "passive"))
      (node (ref "C567") (pin "2") (pinfunction "2_2") (pintype "passive"))
      (node (ref "C568") (pin "2") (pinfunction "2_2") (pintype "passive"))
      (node (ref "C569") (pin "2") (pinfunction "2_2") (pintype "passive"))
      (node (ref "C570") (pin "1") (pinfunction "1_1") (pintype "passive"))
      (node (ref "D47") (pin "C5") (pinfunction "GVI/MIPI_AVDD_1V1_3_C5") (pintype "passive"))
      (node (ref "D47") (pin "D4") (pinfunction "GVI/MIPI_AVDD_1V1_1_D4") (pintype "passive"))
      (node (ref "D47") (pin "E3") (pinfunction "GVI/MIPI_AVDD_1V1_2_E3") (pintype "passive"))
      (node (ref "D47") (pin "F3") (pinfunction "GVI/MIPI_AVDD_1V1_4_F3") (pintype "passive"))
      (node (ref "D47") (pin "H9") (pinfunction "HDMIRX_DVDD_1V1_1_H9") (pintype "passive"))
      (node (ref "D47") (pin "J4") (pinfunction "HDMITX_DVDD_1V1_2_J4") (pintype "passive"))
      (node (ref "D47") (pin "J5") (pinfunction "HDMITX_DVDD_1V1_3_J5") (pintype "passive"))
      (node (ref "D47") (pin "J6") (pinfunction "HDMITX_DVDD_1V1_1_J6") (pintype "passive"))
      (node (ref "D47") (pin "J7") (pinfunction "PLL_AVDD_1V1_J7") (pintype "passive"))
      (node (ref "D47") (pin "J9") (pinfunction "HDMIRX_DVDD_1V1_2_J9") (pintype "passive"))
    )
    (net (code "104") (name "VCCA3V3_RK628_HDMIRX") (class "Default")
      (node (ref "C550") (pin "2") (pinfunction "2_2") (pintype "passive"))
      (node (ref "C551") (pin "1") (pinfunction "1_1") (pintype "passive"))
      (node (ref "C554") (pin "1") (pinfunction "1_1") (pintype "passive"))
      (node (ref "C555") (pin "2") (pinfunction "2_2") (pintype "passive"))
      (node (ref "C556") (pin "2") (pinfunction "2_2") (pintype "passive"))
      (node (ref "C564") (pin "2") (pinfunction "2_2") (pintype "passive"))
      (node (ref "C566") (pin "1") (pinfunction "1_1") (pintype "passive"))
      (node (ref "D47") (pin "C3") (pinfunction "GVI/MIPI_PLL_AVDD_3V3_C3") (pintype "passive"))
      (node (ref "D47") (pin "D5") (pinfunction "GVI/MIPI_AVDD_3V3_1_D5") (pintype "passive"))
      (node (ref "D47") (pin "E4") (pinfunction "GVI/MIPI_AVDD_3V3_2_E4") (pintype "passive"))
      (node (ref "D47") (pin "J10") (pinfunction "HDMIRX_AVDD_3V3_J10") (pintype "passive"))
      (node (ref "D47") (pin "K4") (pinfunction "HDMITX_AVDD_3V3_K4") (pintype "passive"))
      (node (ref "D47") (pin "M10") (pinfunction "PLL_AVDD_3V3_M10") (pintype "passive"))
    )
    (net (code "105") (name "unconnected-(D47-GPIO0_A5-PadH3)") (class "Default")
      (node (ref "D47") (pin "H3") (pinfunction "GPIO0_A5_H3") (pintype "passive+no_connect"))
    )
    (net (code "106") (name "unconnected-(D47-GPIO0_A6-PadH2)") (class "Default")
      (node (ref "D47") (pin "H2") (pinfunction "GPIO0_A6_H2") (pintype "passive+no_connect"))
    )
    (net (code "107") (name "unconnected-(D47-GPIO0_A7-PadH1)") (class "Default")
      (node (ref "D47") (pin "H1") (pinfunction "GPIO0_A7_H1") (pintype "passive+no_connect"))
    )
    (net (code "108") (name "unconnected-(D47-GPIO1_A0-PadH7)") (class "Default")
      (node (ref "D47") (pin "H7") (pinfunction "GPIO1_A0_H7") (pintype "passive+no_connect"))
    )
    (net (code "109") (name "unconnected-(D47-GPIO1_A1_d-PadH8)") (class "Default")
      (node (ref "D47") (pin "H8") (pinfunction "GPIO1_A1_d_H8") (pintype "passive+no_connect"))
    )
    (net (code "110") (name "unconnected-(D47-GPIO2_A0-PadG10)") (class "Default")
      (node (ref "D47") (pin "G10") (pinfunction "GPIO2_A0_G10") (pintype "passive+no_connect"))
    )
    (net (code "111") (name "unconnected-(D47-GPIO2_A1-PadG11)") (class "Default")
      (node (ref "D47") (pin "G11") (pinfunction "GPIO2_A1_G11") (pintype "passive+no_connect"))
    )
    (net (code "112") (name "unconnected-(D47-GPIO2_A2-PadG12)") (class "Default")
      (node (ref "D47") (pin "G12") (pinfunction "GPIO2_A2_G12") (pintype "passive+no_connect"))
    )
    (net (code "113") (name "unconnected-(D47-GPIO2_A3-PadF9)") (class "Default")
      (node (ref "D47") (pin "F9") (pinfunction "GPIO2_A3_F9") (pintype "passive+no_connect"))
    )
    (net (code "114") (name "unconnected-(D47-GPIO2_A4-PadF12)") (class "Default")
      (node (ref "D47") (pin "F12") (pinfunction "GPIO2_A4_F12") (pintype "passive+no_connect"))
    )
    (net (code "115") (name "unconnected-(D47-GPIO2_A5-PadF11)") (class "Default")
      (node (ref "D47") (pin "F11") (pinfunction "GPIO2_A5_F11") (pintype "passive+no_connect"))
    )
    (net (code "116") (name "unconnected-(D47-GPIO2_A6-PadF10)") (class "Default")
      (node (ref "D47") (pin "F10") (pinfunction "GPIO2_A6_F10") (pintype "passive+no_connect"))
    )
    (net (code "117") (name "unconnected-(D47-GPIO2_A7-PadE10)") (class "Default")
      (node (ref "D47") (pin "E10") (pinfunction "GPIO2_A7_E10") (pintype "passive+no_connect"))
    )
    (net (code "118") (name "unconnected-(D47-GPIO2_B0-PadE12)") (class "Default")
      (node (ref "D47") (pin "E12") (pinfunction "GPIO2_B0_E12") (pintype "passive+no_connect"))
    )
    (net (code "119") (name "unconnected-(D47-GPIO2_B1-PadE11)") (class "Default")
      (node (ref "D47") (pin "E11") (pinfunction "GPIO2_B1_E11") (pintype "passive+no_connect"))
    )
    (net (code "120") (name "unconnected-(D47-GPIO2_B2-PadD10)") (class "Default")
      (node (ref "D47") (pin "D10") (pinfunction "GPIO2_B2_D10") (pintype "passive+no_connect"))
    )
    (net (code "121") (name "unconnected-(D47-GPIO2_B3-PadD11)") (class "Default")
      (node (ref "D47") (pin "D11") (pinfunction "GPIO2_B3_D11") (pintype "passive+no_connect"))
    )
    (net (code "122") (name "unconnected-(D47-GPIO2_B4-PadC11)") (class "Default")
      (node (ref "D47") (pin "C11") (pinfunction "GPIO2_B4_C11") (pintype "passive+no_connect"))
    )
    (net (code "123") (name "unconnected-(D47-GPIO2_B5-PadD12)") (class "Default")
      (node (ref "D47") (pin "D12") (pinfunction "GPIO2_B5_D12") (pintype "passive+no_connect"))
    )
    (net (code "124") (name "unconnected-(D47-GPIO2_B6-PadC12)") (class "Default")
      (node (ref "D47") (pin "C12") (pinfunction "GPIO2_B6_C12") (pintype "passive+no_connect"))
    )
    (net (code "125") (name "unconnected-(D47-GPIO2_B7-PadB12)") (class "Default")
      (node (ref "D47") (pin "B12") (pinfunction "GPIO2_B7_B12") (pintype "passive+no_connect"))
    )
    (net (code "126") (name "unconnected-(D47-GPIO2_C0-PadB11)") (class "Default")
      (node (ref "D47") (pin "B11") (pinfunction "GPIO2_C0_B11") (pintype "passive+no_connect"))
    )
    (net (code "127") (name "unconnected-(D47-GPIO2_C1-PadA11)") (class "Default")
      (node (ref "D47") (pin "A11") (pinfunction "GPIO2_C1_A11") (pintype "passive+no_connect"))
    )
    (net (code "128") (name "unconnected-(D47-GPIO2_C2-PadC10)") (class "Default")
      (node (ref "D47") (pin "C10") (pinfunction "GPIO2_C2_C10") (pintype "passive+no_connect"))
    )
    (net (code "129") (name "unconnected-(D47-GPIO2_C3-PadB10)") (class "Default")
      (node (ref "D47") (pin "B10") (pinfunction "GPIO2_C3_B10") (pintype "passive+no_connect"))
    )
    (net (code "130") (name "unconnected-(D47-GPIO2_C4-PadA10)") (class "Default")
      (node (ref "D47") (pin "A10") (pinfunction "GPIO2_C4_A10") (pintype "passive+no_connect"))
    )
    (net (code "131") (name "unconnected-(D47-GPIO2_C5-PadD9)") (class "Default")
      (node (ref "D47") (pin "D9") (pinfunction "GPIO2_C5_D9") (pintype "passive+no_connect"))
    )
    (net (code "132") (name "unconnected-(D47-GPIO2_C6-PadC9)") (class "Default")
      (node (ref "D47") (pin "C9") (pinfunction "GPIO2_C6_C9") (pintype "passive+no_connect"))
    )
    (net (code "133") (name "unconnected-(D47-GPIO2_C7-PadC8)") (class "Default")
      (node (ref "D47") (pin "C8") (pinfunction "GPIO2_C7_C8") (pintype "passive+no_connect"))
    )
    (net (code "134") (name "unconnected-(D47-GPIO3_A0-PadB9)") (class "Default")
      (node (ref "D47") (pin "B9") (pinfunction "GPIO3_A0_B9") (pintype "passive+no_connect"))
    )
    (net (code "135") (name "unconnected-(D47-GPIO3_A1-PadA8)") (class "Default")
      (node (ref "D47") (pin "A8") (pinfunction "GPIO3_A1_A8") (pintype "passive+no_connect"))
    )
    (net (code "136") (name "unconnected-(D47-GPIO3_A3-PadB8)") (class "Default")
      (node (ref "D47") (pin "B8") (pinfunction "GPIO3_A3_B8") (pintype "passive+no_connect"))
    )
    (net (code "137") (name "unconnected-(D47-GPIO3_B0-PadA9)") (class "Default")
      (node (ref "D47") (pin "A9") (pinfunction "GPIO3_B0_A9") (pintype "passive+no_connect"))
    )
    (net (code "138") (name "unconnected-(D47-VCCIO2_1-PadE8)") (class "Default")
      (node (ref "D47") (pin "E8") (pinfunction "VCCIO2_1_E8") (pintype "passive+no_connect"))
    )
    (net (code "139") (name "unconnected-(D47-VCCIO2_2-PadF8)") (class "Default")
      (node (ref "D47") (pin "F8") (pinfunction "VCCIO2_2_F8") (pintype "passive+no_connect"))
    )
    (net (code "140") (name "unconnected-(X31-Pad28)") (class "Default")
      (node (ref "X31") (pin "28") (pinfunction "28_28") (pintype "passive+no_connect"))
    )
    (net (code "141") (name "unconnected-(X31-Pad29)") (class "Default")
      (node (ref "X31") (pin "29") (pinfunction "29_29") (pintype "passive+no_connect"))
    )
    (net (code "142") (name "unconnected-(X31-Pad30)") (class "Default")
      (node (ref "X31") (pin "30") (pinfunction "30_30") (pintype "passive+no_connect"))
    )
    (net (code "143") (name "unconnected-(X31-Pad31)") (class "Default")
      (node (ref "X31") (pin "31") (pinfunction "31_31") (pintype "passive+no_connect"))
    )
    (net (code "144") (name "unconnected-(X31-Pad32)") (class "Default")
      (node (ref "X31") (pin "32") (pinfunction "32_32") (pintype "passive+no_connect"))
    )
    (net (code "145") (name "unconnected-(X31-Pad33)") (class "Default")
      (node (ref "X31") (pin "33") (pinfunction "33_33") (pintype "passive+no_connect"))
    )
    (net (code "146") (name "unconnected-(X31-Pad34)") (class "Default")
      (node (ref "X31") (pin "34") (pinfunction "34_34") (pintype "passive+no_connect"))
    )
    (net (code "147") (name "unconnected-(X31-Pad35)") (class "Default")
      (node (ref "X31") (pin "35") (pinfunction "35_35") (pintype "passive+no_connect"))
    )
    (net (code "148") (name "unconnected-(X31-Pad36)") (class "Default")
      (node (ref "X31") (pin "36") (pinfunction "36_36") (pintype "passive+no_connect"))
    )
    (net (code "149") (name "unconnected-(X31-Pad37)") (class "Default")
      (node (ref "X31") (pin "37") (pinfunction "37_37") (pintype "passive+no_connect"))
    )
    (net (code "150") (name "unconnected-(X31-Pad38)") (class "Default")
      (node (ref "X31") (pin "38") (pinfunction "38_38") (pintype "passive+no_connect"))
    )
    (net (code "151") (name "unconnected-(X31-Pad43)") (class "Default")
      (node (ref "X31") (pin "43") (pinfunction "43_43") (pintype "passive+no_connect"))
    )
  )
)
